# tl.net
KiCad netlist of a schematic drawn in Altium Designer
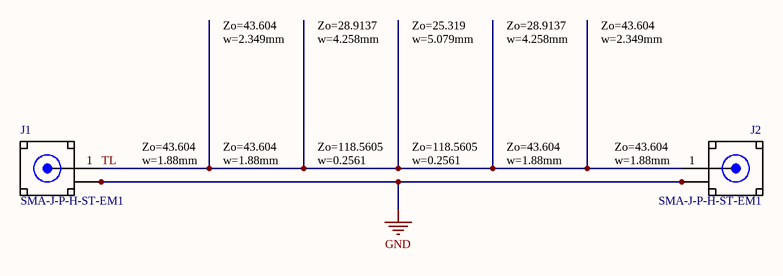
[diagram p0: tl.SchDoc]

(export (version "E")
  (design (tool "Eeschema 10.0.6"))
  (components
    (comp (ref "J1")
      (value "SMA-J-P-H-ST-EM1")
      (footprint "SMA-J-P-H-ST-EM1_SMA-J-P-H-ST-EM1(Primary)")
      (description "SMA Connector Jack, Female Socket 50Ohm Board Edge, End Launch Solder")
      (fields (field (name "MF") "Samtec"))
      (libsource (lib "Kazoo Hardware Library") (part "SMA-J-P-H-ST-EM1"))
    )
    (comp (ref "J2")
      (value "SMA-J-P-H-ST-EM1")
      (footprint "SMA-J-P-H-ST-EM1_SMA-J-P-H-ST-EM1(Primary)")
      (description "SMA Connector Jack, Female Socket 50Ohm Board Edge, End Launch Solder")
      (fields (field (name "MF") "Samtec"))
      (libsource (lib "Kazoo Hardware Library") (part "SMA-J-P-H-ST-EM1"))
    )
  )
  (nets
    (net (code "1") (name "/TL") (class "Default")
      (node (ref "J1") (pin "1") (pinfunction "SIGNAL_1") (pintype "passive"))
      (node (ref "J2") (pin "1") (pinfunction "SIGNAL_1") (pintype "passive"))
    )
    (net (code "2") (name "GND") (class "Default")
      (node (ref "J1") (pin "2_1") (pinfunction "GND_2_1") (pintype "power_in"))
      (node (ref "J1") (pin "2_2") (pinfunction "GND_2_2") (pintype "power_in"))
      (node (ref "J1") (pin "3_1") (pinfunction "GND_3_1") (pintype "power_in"))
      (node (ref "J1") (pin "3_2") (pinfunction "GND_3_2") (pintype "power_in"))
      (node (ref "J2") (pin "2_1") (pinfunction "GND_2_1") (pintype "power_in"))
      (node (ref "J2") (pin "2_2") (pinfunction "GND_2_2") (pintype "power_in"))
      (node (ref "J2") (pin "3_1") (pinfunction "GND_3_1") (pintype "power_in"))
      (node (ref "J2") (pin "3_2") (pinfunction "GND_3_2") (pintype "power_in"))
    )
  )
)
